# synchronization_clock_-_physical_connect.net
KiCad netlist of a schematic drawn in EAGLE
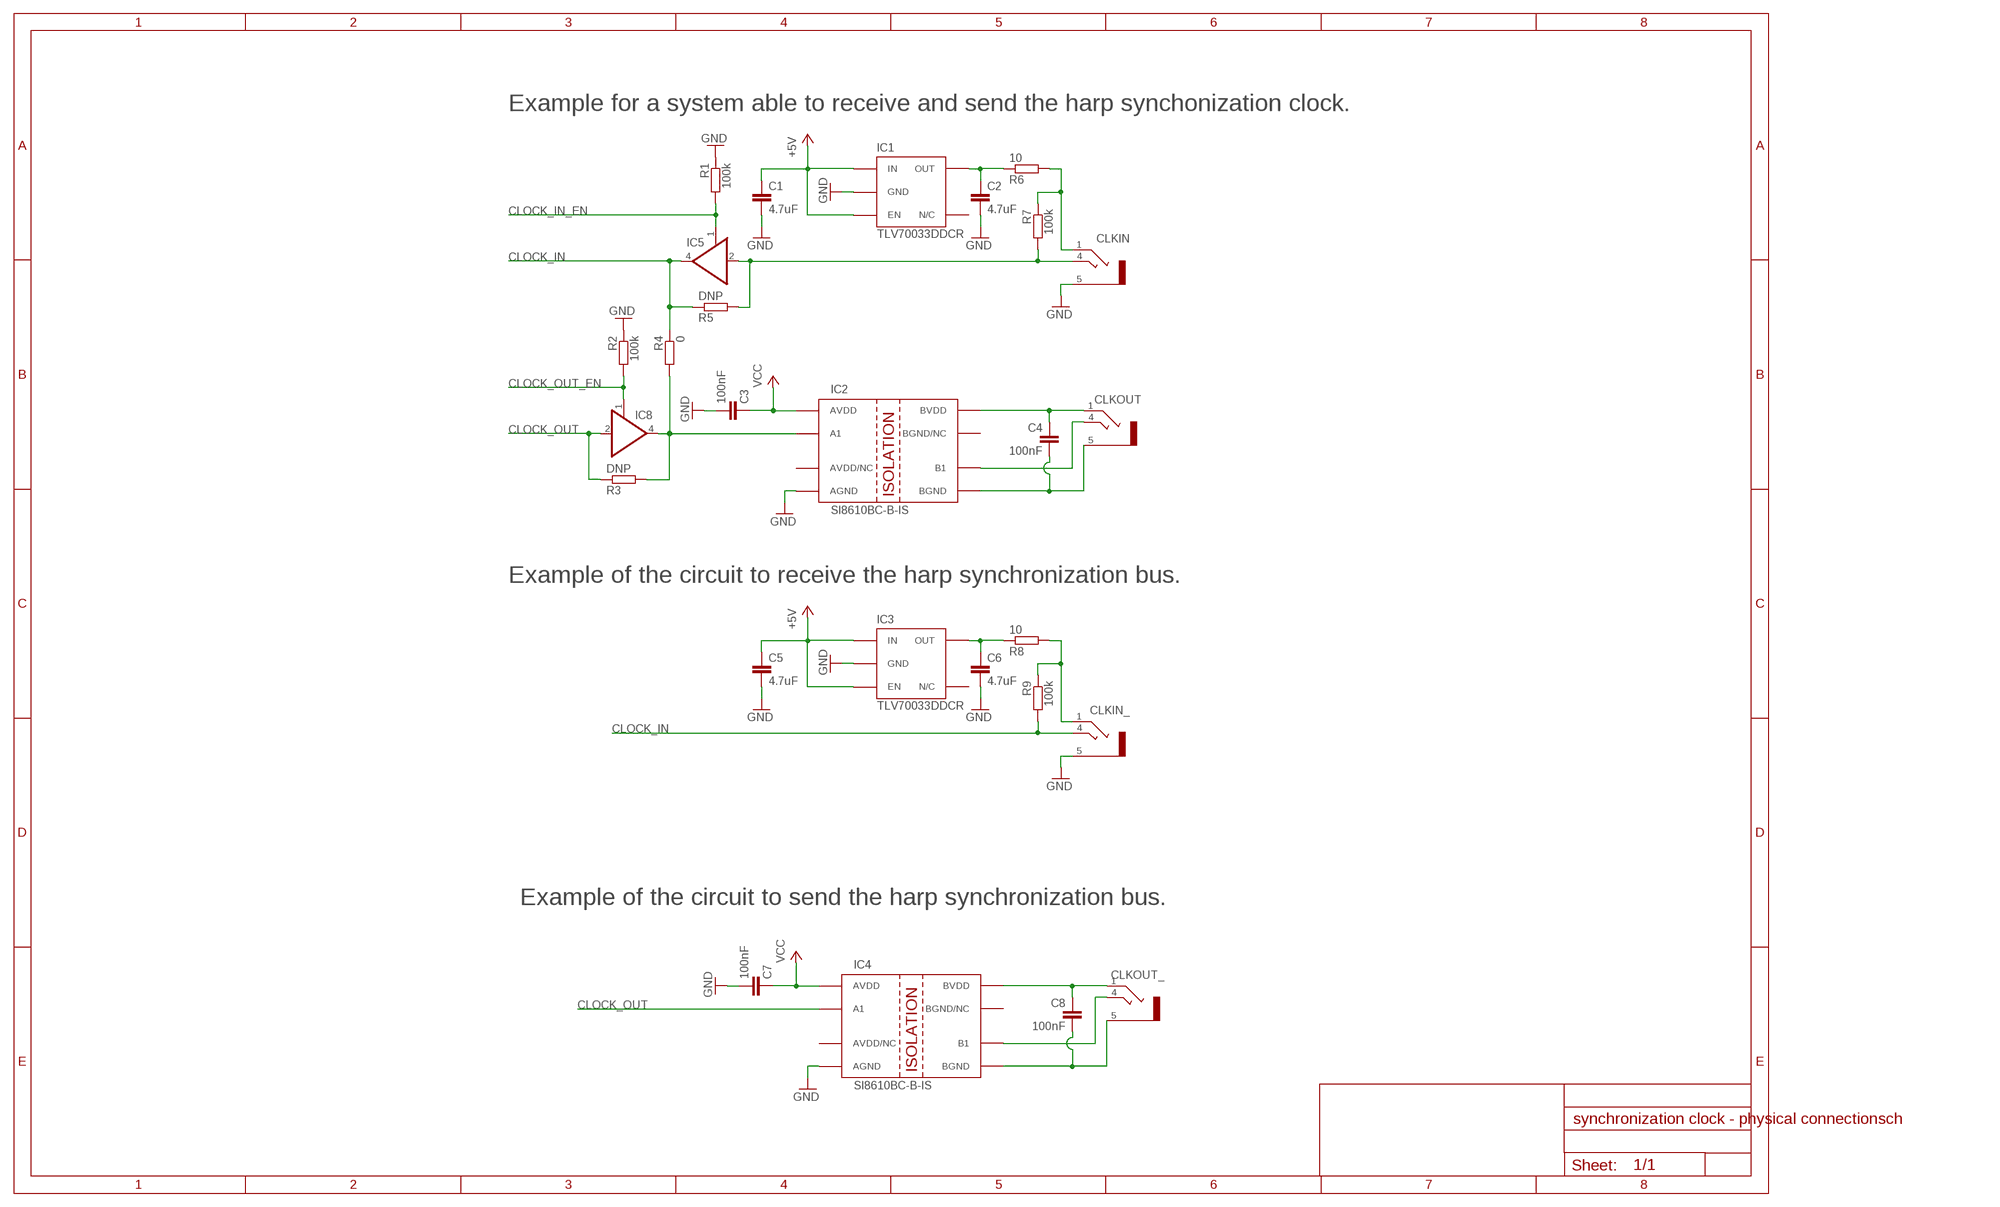
[diagram p0: schematic, sheet 1]

(export (version "E")
  (design (tool "Eeschema 10.0.6"))
  (components
    (comp (ref "C1")
      (value "4.7uF")
      (footprint "eagle-import:C0603")
      (libsource (lib "eagle-import") (part "C-EUC0603"))
    )
    (comp (ref "C2")
      (value "4.7uF")
      (footprint "eagle-import:C0603")
      (libsource (lib "eagle-import") (part "C-EUC0603"))
    )
    (comp (ref "C3")
      (value "100nF")
      (footprint "eagle-import:C0402")
      (libsource (lib "eagle-import") (part "C-EUC0402"))
    )
    (comp (ref "C4")
      (value "100nF")
      (footprint "eagle-import:C0402")
      (libsource (lib "eagle-import") (part "C-EUC0402"))
    )
    (comp (ref "C5")
      (value "4.7uF")
      (footprint "eagle-import:C0603")
      (libsource (lib "eagle-import") (part "C-EUC0603"))
    )
    (comp (ref "C6")
      (value "4.7uF")
      (footprint "eagle-import:C0603")
      (libsource (lib "eagle-import") (part "C-EUC0603"))
    )
    (comp (ref "C7")
      (value "100nF")
      (footprint "eagle-import:C0402")
      (libsource (lib "eagle-import") (part "C-EUC0402"))
    )
    (comp (ref "C8")
      (value "100nF")
      (footprint "eagle-import:C0402")
      (libsource (lib "eagle-import") (part "C-EUC0402"))
    )
    (comp (ref "CLKIN")
      (value "STEREO_JACK")
      (footprint "eagle-import:35RASMT2BHNTRX")
      (libsource (lib "eagle-import") (part "STEREO_JACK"))
    )
    (comp (ref "CLKIN_")
      (value "STEREO_JACK")
      (footprint "eagle-import:35RASMT2BHNTRX")
      (libsource (lib "eagle-import") (part "STEREO_JACK"))
    )
    (comp (ref "CLKOUT")
      (value "STEREO_JACK")
      (footprint "eagle-import:35RASMT2BHNTRX")
      (libsource (lib "eagle-import") (part "STEREO_JACK"))
    )
    (comp (ref "CLKOUT_")
      (value "STEREO_JACK")
      (footprint "eagle-import:35RASMT2BHNTRX")
      (libsource (lib "eagle-import") (part "STEREO_JACK"))
    )
    (comp (ref "IC1")
      (value "TLV70033DDCR")
      (footprint "eagle-import:TSOT23-5")
      (libsource (lib "eagle-import") (part "TLV700XX"))
    )
    (comp (ref "IC2")
      (value "SI8610BC-B-IS")
      (footprint "eagle-import:SO-08")
      (libsource (lib "eagle-import") (part "SI8610"))
    )
    (comp (ref "IC3")
      (value "TLV70033DDCR")
      (footprint "eagle-import:TSOT23-5")
      (libsource (lib "eagle-import") (part "TLV700XX"))
    )
    (comp (ref "IC4")
      (value "SI8610BC-B-IS")
      (footprint "eagle-import:SO-08")
      (libsource (lib "eagle-import") (part "SI8610"))
    )
    (comp (ref "IC5")
      (value "74AHC1G126DCK")
      (footprint "eagle-import:SC70-5")
      (libsource (lib "eagle-import") (part "741G126DCKAHC"))
    )
    (comp (ref "IC8")
      (value "74AHC1G126DCK")
      (footprint "eagle-import:SC70-5")
      (libsource (lib "eagle-import") (part "741G126DCKAHC"))
    )
    (comp (ref "R1")
      (value "100k")
      (footprint "eagle-import:R0402")
      (libsource (lib "eagle-import") (part "R-EU_R0402"))
    )
    (comp (ref "R2")
      (value "100k")
      (footprint "eagle-import:R0402")
      (libsource (lib "eagle-import") (part "R-EU_R0402"))
    )
    (comp (ref "R3")
      (value "DNP")
      (footprint "eagle-import:R0402")
      (libsource (lib "eagle-import") (part "R-EU_R0402"))
    )
    (comp (ref "R4")
      (value "0")
      (footprint "eagle-import:R0402")
      (libsource (lib "eagle-import") (part "R-EU_R0402"))
    )
    (comp (ref "R5")
      (value "DNP")
      (footprint "eagle-import:R0402")
      (libsource (lib "eagle-import") (part "R-EU_R0402"))
    )
    (comp (ref "R6")
      (value "10")
      (footprint "eagle-import:R0402")
      (libsource (lib "eagle-import") (part "R-EU_R0402"))
    )
    (comp (ref "R7")
      (value "100k")
      (footprint "eagle-import:R0402")
      (libsource (lib "eagle-import") (part "R-EU_R0402"))
    )
    (comp (ref "R8")
      (value "10")
      (footprint "eagle-import:R0402")
      (libsource (lib "eagle-import") (part "R-EU_R0402"))
    )
    (comp (ref "R9")
      (value "100k")
      (footprint "eagle-import:R0402")
      (libsource (lib "eagle-import") (part "R-EU_R0402"))
    )
  )
  (nets
    (net (code "1") (name "+5V") (class "Default")
      (node (ref "C1") (pin "1") (pinfunction "1_1") (pintype "passive"))
      (node (ref "C5") (pin "1") (pinfunction "1_1") (pintype "passive"))
      (node (ref "IC1") (pin "1") (pinfunction "IN_1") (pintype "bidirectional"))
      (node (ref "IC1") (pin "3") (pinfunction "EN_3") (pintype "bidirectional"))
      (node (ref "IC3") (pin "1") (pinfunction "IN_1") (pintype "bidirectional"))
      (node (ref "IC3") (pin "3") (pinfunction "EN_3") (pintype "bidirectional"))
    )
    (net (code "2") (name "/CLOCK_IN") (class "Default")
      (node (ref "CLKIN_") (pin "4") (pinfunction "4_4") (pintype "passive"))
      (node (ref "IC5") (pin "4") (pinfunction "O_4") (pintype "output"))
      (node (ref "R4") (pin "1") (pinfunction "1_1") (pintype "passive"))
      (node (ref "R5") (pin "1") (pinfunction "1_1") (pintype "passive"))
      (node (ref "R9") (pin "2") (pinfunction "2_2") (pintype "passive"))
    )
    (net (code "3") (name "/CLOCK_IN_EN") (class "Default")
      (node (ref "IC5") (pin "1") (pinfunction "OE_1") (pintype "input"))
      (node (ref "R1") (pin "2") (pinfunction "2_2") (pintype "passive"))
    )
    (net (code "4") (name "/CLOCK_OUT") (class "Default")
      (node (ref "IC4") (pin "2") (pinfunction "A1_2") (pintype "bidirectional"))
      (node (ref "IC8") (pin "2") (pinfunction "I_2") (pintype "input"))
      (node (ref "R3") (pin "1") (pinfunction "1_1") (pintype "passive"))
    )
    (net (code "5") (name "/CLOCK_OUT_EN") (class "Default")
      (node (ref "IC8") (pin "1") (pinfunction "OE_1") (pintype "input"))
      (node (ref "R2") (pin "2") (pinfunction "2_2") (pintype "passive"))
    )
    (net (code "6") (name "GND") (class "Default")
      (node (ref "C1") (pin "2") (pinfunction "2_2") (pintype "passive"))
      (node (ref "C2") (pin "2") (pinfunction "2_2") (pintype "passive"))
      (node (ref "C3") (pin "2") (pinfunction "2_2") (pintype "passive"))
      (node (ref "C5") (pin "2") (pinfunction "2_2") (pintype "passive"))
      (node (ref "C6") (pin "2") (pinfunction "2_2") (pintype "passive"))
      (node (ref "C7") (pin "2") (pinfunction "2_2") (pintype "passive"))
      (node (ref "CLKIN") (pin "5") (pinfunction "5_5") (pintype "passive"))
      (node (ref "CLKIN_") (pin "5") (pinfunction "5_5") (pintype "passive"))
      (node (ref "IC1") (pin "2") (pinfunction "GND_2") (pintype "bidirectional"))
      (node (ref "IC2") (pin "4") (pinfunction "AGND_4") (pintype "bidirectional"))
      (node (ref "IC3") (pin "2") (pinfunction "GND_2") (pintype "bidirectional"))
      (node (ref "IC4") (pin "4") (pinfunction "AGND_4") (pintype "bidirectional"))
      (node (ref "R1") (pin "1") (pinfunction "1_1") (pintype "passive"))
      (node (ref "R2") (pin "1") (pinfunction "1_1") (pintype "passive"))
    )
    (net (code "7") (name "Net-(CLKIN-Pad1)") (class "Default")
      (node (ref "CLKIN") (pin "1") (pinfunction "1_1") (pintype "passive"))
      (node (ref "R6") (pin "2") (pinfunction "2_2") (pintype "passive"))
      (node (ref "R7") (pin "1") (pinfunction "1_1") (pintype "passive"))
    )
    (net (code "8") (name "Net-(CLKIN_-Pad1)") (class "Default")
      (node (ref "CLKIN_") (pin "1") (pinfunction "1_1") (pintype "passive"))
      (node (ref "R8") (pin "2") (pinfunction "2_2") (pintype "passive"))
      (node (ref "R9") (pin "1") (pinfunction "1_1") (pintype "passive"))
    )
    (net (code "9") (name "Net-(IC1-OUT)") (class "Default")
      (node (ref "C2") (pin "1") (pinfunction "1_1") (pintype "passive"))
      (node (ref "IC1") (pin "5") (pinfunction "OUT_5") (pintype "bidirectional"))
      (node (ref "R6") (pin "1") (pinfunction "1_1") (pintype "passive"))
    )
    (net (code "10") (name "Net-(IC2-A1)") (class "Default")
      (node (ref "IC2") (pin "2") (pinfunction "A1_2") (pintype "bidirectional"))
      (node (ref "IC8") (pin "4") (pinfunction "O_4") (pintype "output"))
      (node (ref "R3") (pin "2") (pinfunction "2_2") (pintype "passive"))
      (node (ref "R4") (pin "2") (pinfunction "2_2") (pintype "passive"))
    )
    (net (code "11") (name "Net-(IC2-B1)") (class "Default")
      (node (ref "CLKOUT") (pin "4") (pinfunction "4_4") (pintype "passive"))
      (node (ref "IC2") (pin "6") (pinfunction "B1_6") (pintype "bidirectional"))
    )
    (net (code "12") (name "Net-(IC2-BGND)") (class "Default")
      (node (ref "C4") (pin "2") (pinfunction "2_2") (pintype "passive"))
      (node (ref "CLKOUT") (pin "5") (pinfunction "5_5") (pintype "passive"))
      (node (ref "IC2") (pin "5") (pinfunction "BGND_5") (pintype "bidirectional"))
    )
    (net (code "13") (name "Net-(IC2-BVDD)") (class "Default")
      (node (ref "C4") (pin "1") (pinfunction "1_1") (pintype "passive"))
      (node (ref "CLKOUT") (pin "1") (pinfunction "1_1") (pintype "passive"))
      (node (ref "IC2") (pin "8") (pinfunction "BVDD_8") (pintype "bidirectional"))
    )
    (net (code "14") (name "Net-(IC3-OUT)") (class "Default")
      (node (ref "C6") (pin "1") (pinfunction "1_1") (pintype "passive"))
      (node (ref "IC3") (pin "5") (pinfunction "OUT_5") (pintype "bidirectional"))
      (node (ref "R8") (pin "1") (pinfunction "1_1") (pintype "passive"))
    )
    (net (code "15") (name "Net-(IC4-B1)") (class "Default")
      (node (ref "CLKOUT_") (pin "4") (pinfunction "4_4") (pintype "passive"))
      (node (ref "IC4") (pin "6") (pinfunction "B1_6") (pintype "bidirectional"))
    )
    (net (code "16") (name "Net-(IC4-BGND)") (class "Default")
      (node (ref "C8") (pin "2") (pinfunction "2_2") (pintype "passive"))
      (node (ref "CLKOUT_") (pin "5") (pinfunction "5_5") (pintype "passive"))
      (node (ref "IC4") (pin "5") (pinfunction "BGND_5") (pintype "bidirectional"))
    )
    (net (code "17") (name "Net-(IC4-BVDD)") (class "Default")
      (node (ref "C8") (pin "1") (pinfunction "1_1") (pintype "passive"))
      (node (ref "CLKOUT_") (pin "1") (pinfunction "1_1") (pintype "passive"))
      (node (ref "IC4") (pin "8") (pinfunction "BVDD_8") (pintype "bidirectional"))
    )
    (net (code "18") (name "Net-(IC5A-I)") (class "Default")
      (node (ref "CLKIN") (pin "4") (pinfunction "4_4") (pintype "passive"))
      (node (ref "IC5") (pin "2") (pinfunction "I_2") (pintype "input"))
      (node (ref "R5") (pin "2") (pinfunction "2_2") (pintype "passive"))
      (node (ref "R7") (pin "2") (pinfunction "2_2") (pintype "passive"))
    )
    (net (code "19") (name "VCC") (class "Default")
      (node (ref "C3") (pin "1") (pinfunction "1_1") (pintype "passive"))
      (node (ref "C7") (pin "1") (pinfunction "1_1") (pintype "passive"))
      (node (ref "IC2") (pin "1") (pinfunction "AVDD_1") (pintype "bidirectional"))
      (node (ref "IC4") (pin "1") (pinfunction "AVDD_1") (pintype "bidirectional"))
    )
    (net (code "20") (name "unconnected-(IC1-N{slash}C-Pad4)") (class "Default")
      (node (ref "IC1") (pin "4") (pinfunction "N/C_4") (pintype "bidirectional"))
    )
    (net (code "21") (name "unconnected-(IC2-AVDD{slash}NC-Pad3)") (class "Default")
      (node (ref "IC2") (pin "3") (pinfunction "AVDD/NC_3") (pintype "bidirectional"))
    )
    (net (code "22") (name "unconnected-(IC2-BGND{slash}NC-Pad7)") (class "Default")
      (node (ref "IC2") (pin "7") (pinfunction "BGND/NC_7") (pintype "bidirectional"))
    )
    (net (code "23") (name "unconnected-(IC3-N{slash}C-Pad4)") (class "Default")
      (node (ref "IC3") (pin "4") (pinfunction "N/C_4") (pintype "bidirectional"))
    )
    (net (code "24") (name "unconnected-(IC4-AVDD{slash}NC-Pad3)") (class "Default")
      (node (ref "IC4") (pin "3") (pinfunction "AVDD/NC_3") (pintype "bidirectional"))
    )
    (net (code "25") (name "unconnected-(IC4-BGND{slash}NC-Pad7)") (class "Default")
      (node (ref "IC4") (pin "7") (pinfunction "BGND/NC_7") (pintype "bidirectional"))
    )
  )
)
